# 5V0BUCKFINAL.net
KiCad netlist of a schematic drawn in Altium Designer
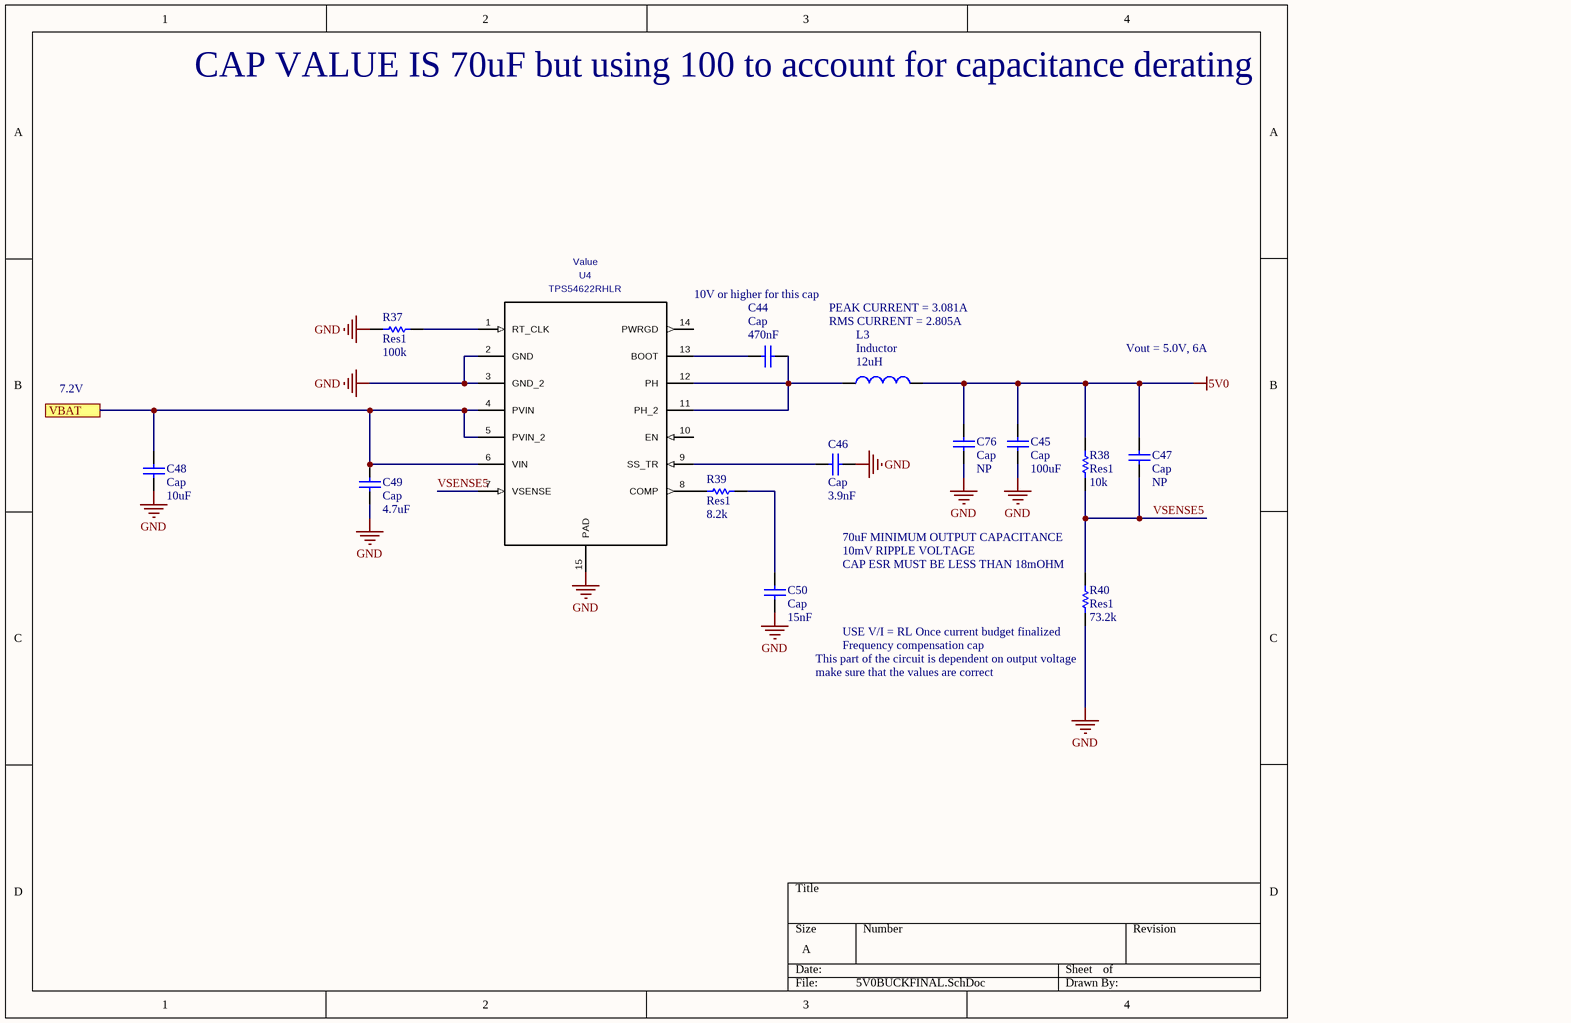
[diagram p0: 5V0BUCKFINAL.SchDoc]

(export (version "E")
  (design (tool "Eeschema 10.0.6"))
  (components
    (comp (ref "C44")
      (value "Cap")
      (footprint "0402-A")
      (description "Capacitor")
      (fields (field (name "ALTIUM_VALUE") "470nF") (field (name "PUBLISHER") "Altium Limited"))
      (libsource (lib "Miscellaneous Devices") (part "Cap"))
    )
    (comp (ref "C45")
      (value "Cap")
      (footprint "C1210")
      (description "Capacitor")
      (fields (field (name "ALTIUM_VALUE") "100uF") (field (name "PUBLISHER") "Altium Limited"))
      (libsource (lib "Miscellaneous Devices") (part "Cap"))
    )
    (comp (ref "C46")
      (value "Cap")
      (footprint "0402-A")
      (description "Capacitor")
      (fields (field (name "ALTIUM_VALUE") "3.9nF") (field (name "PUBLISHER") "Altium Limited"))
      (libsource (lib "Miscellaneous Devices") (part "Cap"))
    )
    (comp (ref "C47")
      (value "Cap")
      (footprint "1608[0603]")
      (description "Capacitor")
      (fields (field (name "ALTIUM_VALUE") "NP") (field (name "PUBLISHER") "Altium Limited"))
      (libsource (lib "Miscellaneous Devices") (part "Cap"))
    )
    (comp (ref "C48")
      (value "Cap")
      (footprint "6-0805_M")
      (description "Capacitor")
      (fields (field (name "ALTIUM_VALUE") "10uF") (field (name "PUBLISHER") "Altium Limited"))
      (libsource (lib "Miscellaneous Devices") (part "Cap"))
    )
    (comp (ref "C49")
      (value "Cap")
      (footprint "6-0805_M")
      (description "Capacitor")
      (fields (field (name "ALTIUM_VALUE") "4.7uF") (field (name "PUBLISHER") "Altium Limited"))
      (libsource (lib "Miscellaneous Devices") (part "Cap"))
    )
    (comp (ref "C50")
      (value "Cap")
      (footprint "0402-A")
      (description "Capacitor")
      (fields (field (name "ALTIUM_VALUE") "15nF") (field (name "PUBLISHER") "Altium Limited"))
      (libsource (lib "Miscellaneous Devices") (part "Cap"))
    )
    (comp (ref "C76")
      (value "Cap")
      (footprint "1608[0603]")
      (description "Capacitor")
      (fields (field (name "ALTIUM_VALUE") "NP") (field (name "PUBLISHER") "Altium Limited"))
      (libsource (lib "Miscellaneous Devices") (part "Cap"))
    )
    (comp (ref "L3")
      (value "Inductor")
      (footprint "IND_BOURNS_SRR1260")
      (fields (field (name "ALTIUM_VALUE") "12uH") (field (name "PUBLISHER") "Altium Limited"))
      (libsource (lib "Miscellaneous Devices") (part "Inductor"))
    )
    (comp (ref "R37")
      (value "Res1")
      (footprint "0402-A")
      (description "Resistor")
      (fields (field (name "ALTIUM_VALUE") "100k") (field (name "PUBLISHER") "Altium Limited"))
      (libsource (lib "Miscellaneous Devices") (part "Res1"))
    )
    (comp (ref "R38")
      (value "Res1")
      (footprint "0402-A")
      (description "Resistor")
      (fields (field (name "ALTIUM_VALUE") "10k") (field (name "PUBLISHER") "Altium Limited"))
      (libsource (lib "Miscellaneous Devices") (part "Res1"))
    )
    (comp (ref "R39")
      (value "Res1")
      (footprint "0402-A")
      (description "Resistor")
      (fields (field (name "ALTIUM_VALUE") "8.2k") (field (name "PUBLISHER") "Altium Limited"))
      (libsource (lib "Miscellaneous Devices") (part "Res1"))
    )
    (comp (ref "R40")
      (value "Res1")
      (footprint "0402-A")
      (description "Resistor 1%")
      (fields (field (name "ALTIUM_VALUE") "73.2k") (field (name "PUBLISHER") "Altium Limited"))
      (libsource (lib "Miscellaneous Devices") (part "Res1"))
    )
    (comp (ref "U4")
      (value "TPS54622RHLR")
      (footprint "RHL0014A")
      (fields (field (name "MANUFACTURER") "Texas Instruments") (field (name "ALTIUM_VALUE") "Value"))
      (libsource (lib "AltiumV15") (part "TPS54622RHLR"))
    )
  )
  (nets
    (net (code "1") (name "/VBAT") (class "Default")
      (node (ref "C48") (pin "2") (pinfunction "2_2") (pintype "passive"))
      (node (ref "C49") (pin "2") (pinfunction "2_2") (pintype "passive"))
      (node (ref "U4") (pin "4") (pinfunction "PVIN_4") (pintype "power_in"))
      (node (ref "U4") (pin "5") (pinfunction "PVIN_2_5") (pintype "power_in"))
      (node (ref "U4") (pin "6") (pinfunction "VIN_6") (pintype "power_in"))
    )
    (net (code "2") (name "/VSENSE5") (class "Default")
      (node (ref "C47") (pin "1") (pinfunction "1_1") (pintype "passive"))
      (node (ref "R38") (pin "2") (pinfunction "2_2") (pintype "passive"))
      (node (ref "R40") (pin "2") (pinfunction "2_2") (pintype "passive"))
      (node (ref "U4") (pin "7") (pinfunction "VSENSE_7") (pintype "input"))
    )
    (net (code "3") (name "5V0") (class "Default")
      (node (ref "C45") (pin "2") (pinfunction "2_2") (pintype "passive"))
      (node (ref "C47") (pin "2") (pinfunction "2_2") (pintype "passive"))
      (node (ref "C76") (pin "2") (pinfunction "2_2") (pintype "passive"))
      (node (ref "L3") (pin "2") (pinfunction "2_2") (pintype "passive"))
      (node (ref "R38") (pin "1") (pinfunction "1_1") (pintype "passive"))
    )
    (net (code "4") (name "GND") (class "Default")
      (node (ref "C45") (pin "1") (pinfunction "1_1") (pintype "passive"))
      (node (ref "C46") (pin "1") (pinfunction "1_1") (pintype "passive"))
      (node (ref "C48") (pin "1") (pinfunction "1_1") (pintype "passive"))
      (node (ref "C49") (pin "1") (pinfunction "1_1") (pintype "passive"))
      (node (ref "C50") (pin "1") (pinfunction "1_1") (pintype "passive"))
      (node (ref "C76") (pin "1") (pinfunction "1_1") (pintype "passive"))
      (node (ref "R37") (pin "1") (pinfunction "1_1") (pintype "passive"))
      (node (ref "R40") (pin "1") (pinfunction "1_1") (pintype "passive"))
      (node (ref "U4") (pin "15") (pinfunction "PAD_15") (pintype "power_in"))
      (node (ref "U4") (pin "2") (pinfunction "GND_2") (pintype "power_in"))
      (node (ref "U4") (pin "3") (pinfunction "GND_2_3") (pintype "power_in"))
    )
    (net (code "5") (name "Net-(C50-Pad2)") (class "Default")
      (node (ref "C50") (pin "2") (pinfunction "2_2") (pintype "passive"))
      (node (ref "R39") (pin "1") (pinfunction "1_1") (pintype "passive"))
    )
    (net (code "6") (name "Net-(U4-BOOT)") (class "Default")
      (node (ref "C44") (pin "1") (pinfunction "1_1") (pintype "passive"))
      (node (ref "U4") (pin "13") (pinfunction "BOOT_13") (pintype "power_in"))
    )
    (net (code "7") (name "Net-(U4-COMP)") (class "Default")
      (node (ref "R39") (pin "2") (pinfunction "2_2") (pintype "passive"))
      (node (ref "U4") (pin "8") (pinfunction "COMP_8") (pintype "output"))
    )
    (net (code "8") (name "Net-(U4-PH)") (class "Default")
      (node (ref "C44") (pin "2") (pinfunction "2_2") (pintype "passive"))
      (node (ref "L3") (pin "1") (pinfunction "1_1") (pintype "passive"))
      (node (ref "U4") (pin "11") (pinfunction "PH_2_11") (pintype "power_in"))
      (node (ref "U4") (pin "12") (pinfunction "PH_12") (pintype "power_in"))
    )
    (net (code "9") (name "Net-(U4-RT_CLK)") (class "Default")
      (node (ref "R37") (pin "2") (pinfunction "2_2") (pintype "passive"))
      (node (ref "U4") (pin "1") (pinfunction "RT_CLK_1") (pintype "input"))
    )
    (net (code "10") (name "Net-(U4-SS_TR)") (class "Default")
      (node (ref "C46") (pin "2") (pinfunction "2_2") (pintype "passive"))
      (node (ref "U4") (pin "9") (pinfunction "SS_TR_9") (pintype "input"))
    )
    (net (code "11") (name "unconnected-(U4-EN-Pad10)") (class "Default")
      (node (ref "U4") (pin "10") (pinfunction "EN_10") (pintype "input"))
    )
    (net (code "12") (name "unconnected-(U4-PWRGD-Pad14)") (class "Default")
      (node (ref "U4") (pin "14") (pinfunction "PWRGD_14") (pintype "output"))
    )
  )
)
